# buffered_mult_rt1_postpwer.net
KiCad netlist of a schematic drawn in EAGLE
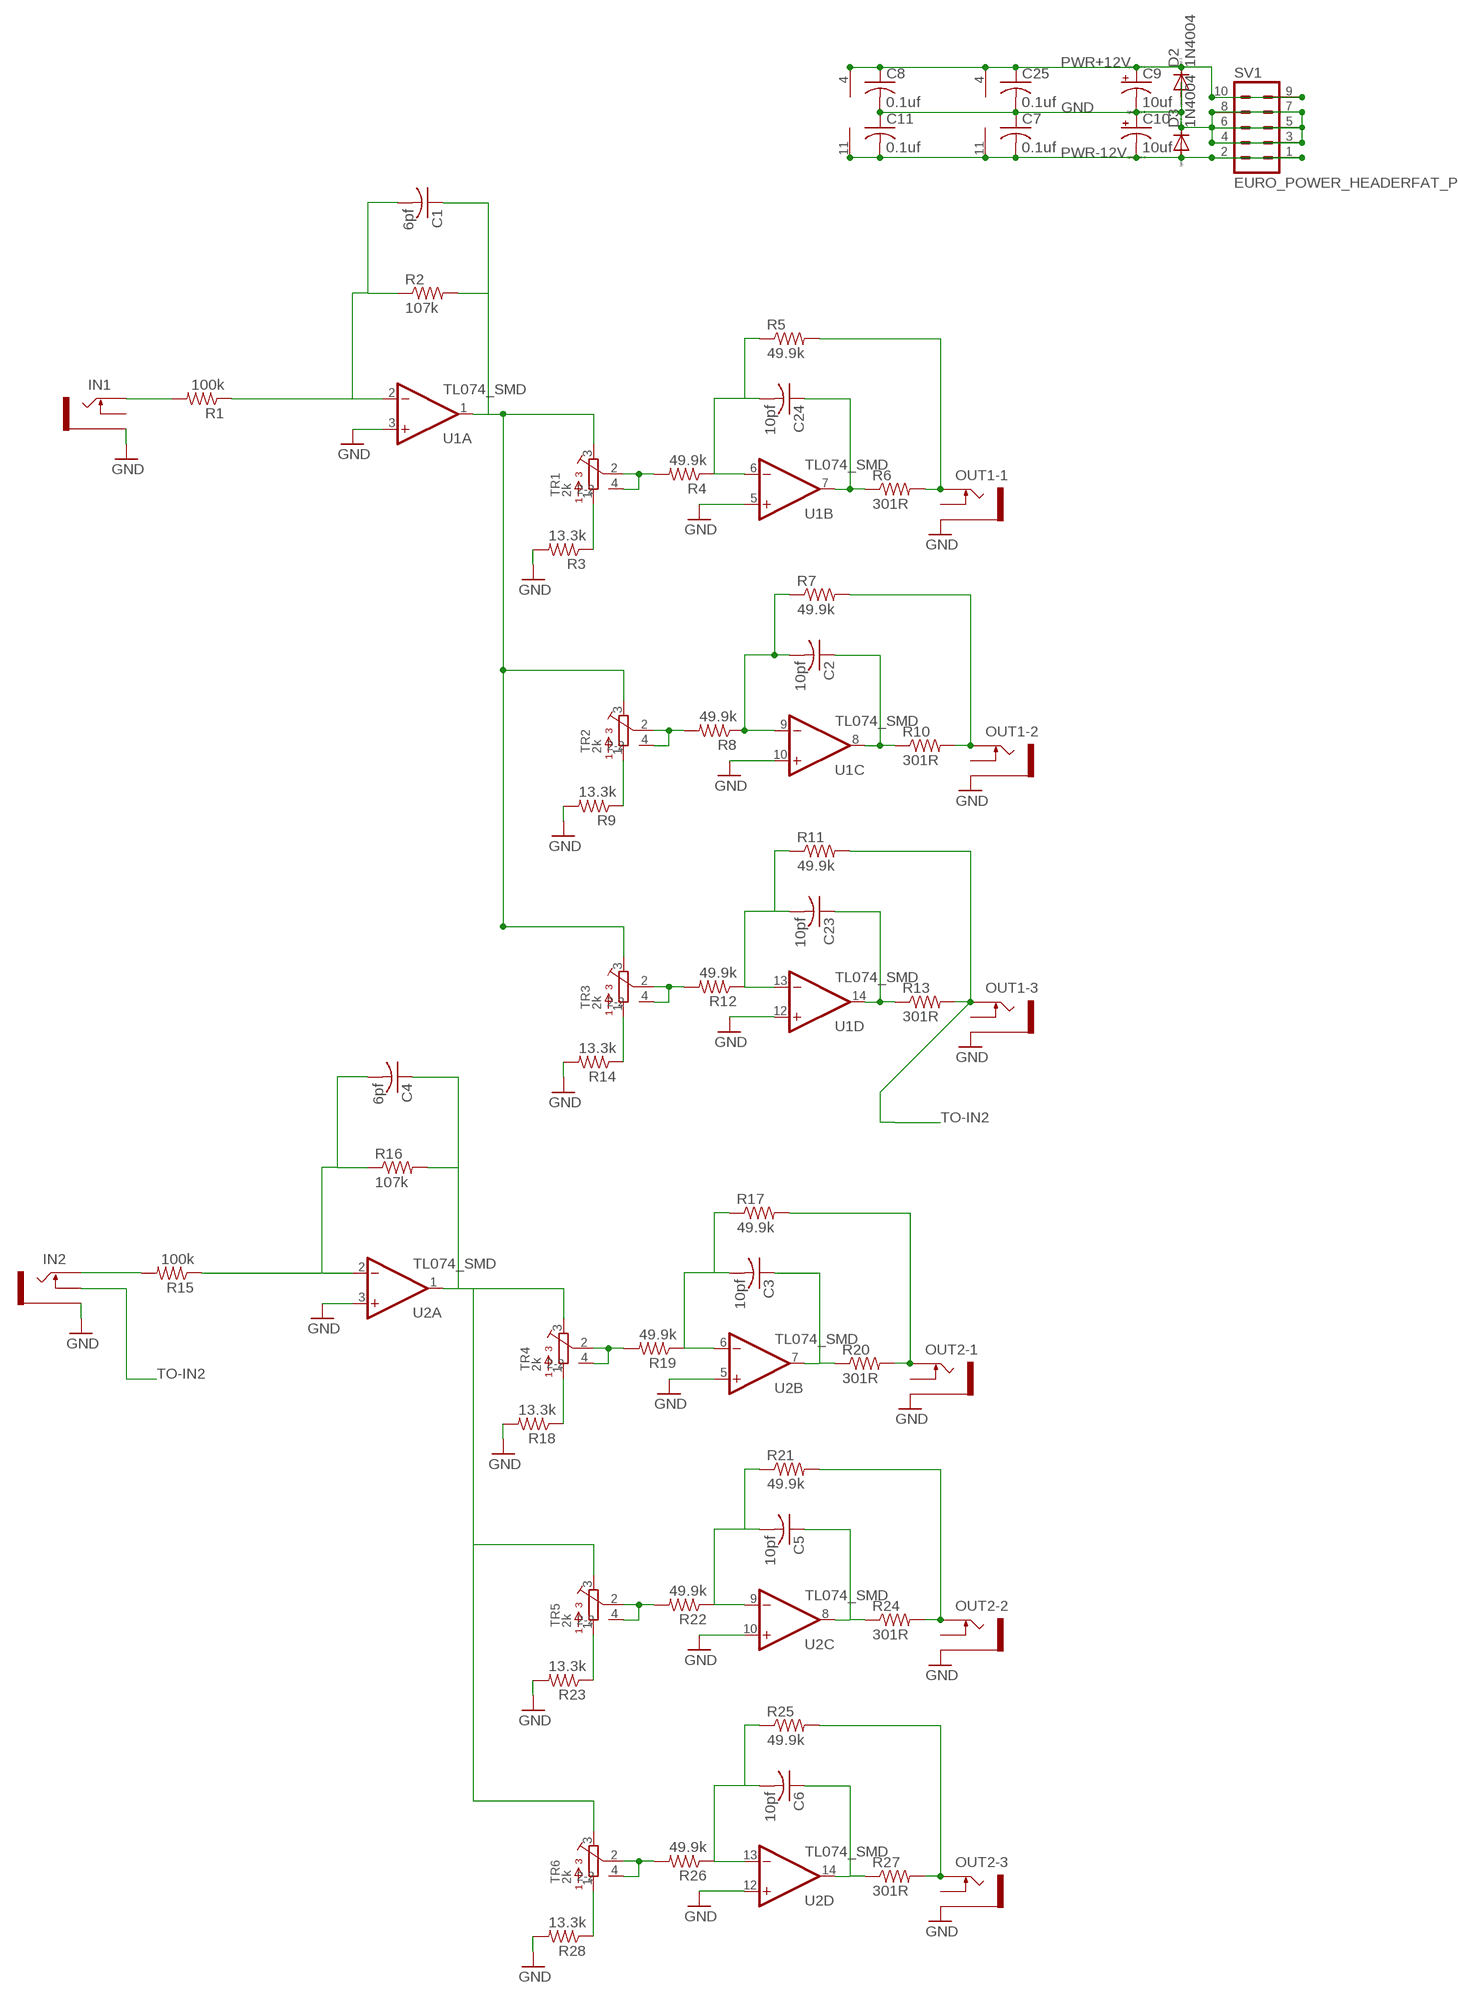
[diagram p0: schematic, sheet 1]

(export (version "E")
  (design (tool "Eeschema 10.0.6"))
  (components
    (comp (ref "C1")
      (value "6pf")
      (footprint "eagle-import:C0603")
      (libsource (lib "eagle-import") (part "C-USC0603"))
    )
    (comp (ref "C2")
      (value "10pf")
      (footprint "eagle-import:C0603")
      (libsource (lib "eagle-import") (part "C-USC0603"))
    )
    (comp (ref "C3")
      (value "10pf")
      (footprint "eagle-import:C0603")
      (libsource (lib "eagle-import") (part "C-USC0603"))
    )
    (comp (ref "C4")
      (value "6pf")
      (footprint "eagle-import:C0603")
      (libsource (lib "eagle-import") (part "C-USC0603"))
    )
    (comp (ref "C5")
      (value "10pf")
      (footprint "eagle-import:C0603")
      (libsource (lib "eagle-import") (part "C-USC0603"))
    )
    (comp (ref "C6")
      (value "10pf")
      (footprint "eagle-import:C0603")
      (libsource (lib "eagle-import") (part "C-USC0603"))
    )
    (comp (ref "C7")
      (value "0.1uf")
      (footprint "eagle-import:C0603")
      (libsource (lib "eagle-import") (part "C-USC0603"))
    )
    (comp (ref "C8")
      (value "0.1uf")
      (footprint "eagle-import:C0603")
      (libsource (lib "eagle-import") (part "C-USC0603"))
    )
    (comp (ref "C9")
      (value "10uf")
      (footprint "eagle-import:153CLV-0505")
      (libsource (lib "eagle-import") (part "CPOL-US153CLV-0505"))
    )
    (comp (ref "C10")
      (value "10uf")
      (footprint "eagle-import:153CLV-0505")
      (libsource (lib "eagle-import") (part "CPOL-US153CLV-0505"))
    )
    (comp (ref "C11")
      (value "0.1uf")
      (footprint "eagle-import:C0603")
      (libsource (lib "eagle-import") (part "C-USC0603"))
    )
    (comp (ref "C23")
      (value "10pf")
      (footprint "eagle-import:C0603")
      (libsource (lib "eagle-import") (part "C-USC0603"))
    )
    (comp (ref "C24")
      (value "10pf")
      (footprint "eagle-import:C0603")
      (libsource (lib "eagle-import") (part "C-USC0603"))
    )
    (comp (ref "C25")
      (value "0.1uf")
      (footprint "eagle-import:C0603")
      (libsource (lib "eagle-import") (part "C-USC0603"))
    )
    (comp (ref "D2")
      (value "1N4004")
      (footprint "eagle-import:DO41-10")
      (libsource (lib "eagle-import") (part "1N4004"))
    )
    (comp (ref "D3")
      (value "1N4004")
      (footprint "eagle-import:DO41-10")
      (libsource (lib "eagle-import") (part "1N4004"))
    )
    (comp (ref "IN1")
      (value "THONKICONNNEW")
      (footprint "eagle-import:WQP-PJ301M-12_JACK")
      (libsource (lib "eagle-import") (part "THONKICONNNEW"))
    )
    (comp (ref "IN2")
      (value "THONKICONNNEW")
      (footprint "eagle-import:WQP-PJ301M-12_JACK")
      (libsource (lib "eagle-import") (part "THONKICONNNEW"))
    )
    (comp (ref "OUT1-1")
      (value "THONKICONNNEW")
      (footprint "eagle-import:WQP-PJ301M-12_JACK")
      (libsource (lib "eagle-import") (part "THONKICONNNEW"))
    )
    (comp (ref "OUT1-2")
      (value "THONKICONNNEW")
      (footprint "eagle-import:WQP-PJ301M-12_JACK")
      (libsource (lib "eagle-import") (part "THONKICONNNEW"))
    )
    (comp (ref "OUT1-3")
      (value "THONKICONNNEW")
      (footprint "eagle-import:WQP-PJ301M-12_JACK")
      (libsource (lib "eagle-import") (part "THONKICONNNEW"))
    )
    (comp (ref "OUT2-1")
      (value "THONKICONNNEW")
      (footprint "eagle-import:WQP-PJ301M-12_JACK")
      (libsource (lib "eagle-import") (part "THONKICONNNEW"))
    )
    (comp (ref "OUT2-2")
      (value "THONKICONNNEW")
      (footprint "eagle-import:WQP-PJ301M-12_JACK")
      (libsource (lib "eagle-import") (part "THONKICONNNEW"))
    )
    (comp (ref "OUT2-3")
      (value "THONKICONNNEW")
      (footprint "eagle-import:WQP-PJ301M-12_JACK")
      (libsource (lib "eagle-import") (part "THONKICONNNEW"))
    )
    (comp (ref "R1")
      (value "100k")
      (footprint "eagle-import:R0603")
      (libsource (lib "eagle-import") (part "R-US_R0603"))
    )
    (comp (ref "R2")
      (value "107k")
      (footprint "eagle-import:R0603")
      (libsource (lib "eagle-import") (part "R-US_R0603"))
    )
    (comp (ref "R3")
      (value "13.3k")
      (footprint "eagle-import:R0603")
      (libsource (lib "eagle-import") (part "R-US_R0603"))
    )
    (comp (ref "R4")
      (value "49.9k")
      (footprint "eagle-import:R0603")
      (libsource (lib "eagle-import") (part "R-US_R0603"))
    )
    (comp (ref "R5")
      (value "49.9k")
      (footprint "eagle-import:R0603")
      (libsource (lib "eagle-import") (part "R-US_R0603"))
    )
    (comp (ref "R6")
      (value "301R")
      (footprint "eagle-import:R0603")
      (libsource (lib "eagle-import") (part "R-US_R0603"))
    )
    (comp (ref "R7")
      (value "49.9k")
      (footprint "eagle-import:R0603")
      (libsource (lib "eagle-import") (part "R-US_R0603"))
    )
    (comp (ref "R8")
      (value "49.9k")
      (footprint "eagle-import:R0603")
      (libsource (lib "eagle-import") (part "R-US_R0603"))
    )
    (comp (ref "R9")
      (value "13.3k")
      (footprint "eagle-import:R0603")
      (libsource (lib "eagle-import") (part "R-US_R0603"))
    )
    (comp (ref "R10")
      (value "301R")
      (footprint "eagle-import:R0603")
      (libsource (lib "eagle-import") (part "R-US_R0603"))
    )
    (comp (ref "R11")
      (value "49.9k")
      (footprint "eagle-import:R0603")
      (libsource (lib "eagle-import") (part "R-US_R0603"))
    )
    (comp (ref "R12")
      (value "49.9k")
      (footprint "eagle-import:R0603")
      (libsource (lib "eagle-import") (part "R-US_R0603"))
    )
    (comp (ref "R13")
      (value "301R")
      (footprint "eagle-import:R0603")
      (libsource (lib "eagle-import") (part "R-US_R0603"))
    )
    (comp (ref "R14")
      (value "13.3k")
      (footprint "eagle-import:R0603")
      (libsource (lib "eagle-import") (part "R-US_R0603"))
    )
    (comp (ref "R15")
      (value "100k")
      (footprint "eagle-import:R0603")
      (libsource (lib "eagle-import") (part "R-US_R0603"))
    )
    (comp (ref "R16")
      (value "107k")
      (footprint "eagle-import:R0603")
      (libsource (lib "eagle-import") (part "R-US_R0603"))
    )
    (comp (ref "R17")
      (value "49.9k")
      (footprint "eagle-import:R0603")
      (libsource (lib "eagle-import") (part "R-US_R0603"))
    )
    (comp (ref "R18")
      (value "13.3k")
      (footprint "eagle-import:R0603")
      (libsource (lib "eagle-import") (part "R-US_R0603"))
    )
    (comp (ref "R19")
      (value "49.9k")
      (footprint "eagle-import:R0603")
      (libsource (lib "eagle-import") (part "R-US_R0603"))
    )
    (comp (ref "R20")
      (value "301R")
      (footprint "eagle-import:R0603")
      (libsource (lib "eagle-import") (part "R-US_R0603"))
    )
    (comp (ref "R21")
      (value "49.9k")
      (footprint "eagle-import:R0603")
      (libsource (lib "eagle-import") (part "R-US_R0603"))
    )
    (comp (ref "R22")
      (value "49.9k")
      (footprint "eagle-import:R0603")
      (libsource (lib "eagle-import") (part "R-US_R0603"))
    )
    (comp (ref "R23")
      (value "13.3k")
      (footprint "eagle-import:R0603")
      (libsource (lib "eagle-import") (part "R-US_R0603"))
    )
    (comp (ref "R24")
      (value "301R")
      (footprint "eagle-import:R0603")
      (libsource (lib "eagle-import") (part "R-US_R0603"))
    )
    (comp (ref "R25")
      (value "49.9k")
      (footprint "eagle-import:R0603")
      (libsource (lib "eagle-import") (part "R-US_R0603"))
    )
    (comp (ref "R26")
      (value "49.9k")
      (footprint "eagle-import:R0603")
      (libsource (lib "eagle-import") (part "R-US_R0603"))
    )
    (comp (ref "R27")
      (value "301R")
      (footprint "eagle-import:R0603")
      (libsource (lib "eagle-import") (part "R-US_R0603"))
    )
    (comp (ref "R28")
      (value "13.3k")
      (footprint "eagle-import:R0603")
      (libsource (lib "eagle-import") (part "R-US_R0603"))
    )
    (comp (ref "SV1")
      (value "EURO_POWER_HEADERFAT_PADS")
      (footprint "eagle-import:EURO_PWR_HEADER_FAT")
      (libsource (lib "eagle-import") (part "EURO_POWER_HEADERFAT_PADS"))
    )
    (comp (ref "TR1")
      (value "2k")
      (footprint "eagle-import:BOURNS_3362P_TRIMMER")
      (libsource (lib "eagle-import") (part "BOURNS_3362P_TRIMMERP"))
    )
    (comp (ref "TR2")
      (value "2k")
      (footprint "eagle-import:BOURNS_3362P_TRIMMER")
      (libsource (lib "eagle-import") (part "BOURNS_3362P_TRIMMERP"))
    )
    (comp (ref "TR3")
      (value "2k")
      (footprint "eagle-import:BOURNS_3362P_TRIMMER")
      (libsource (lib "eagle-import") (part "BOURNS_3362P_TRIMMERP"))
    )
    (comp (ref "TR4")
      (value "2k")
      (footprint "eagle-import:BOURNS_3362P_TRIMMER")
      (libsource (lib "eagle-import") (part "BOURNS_3362P_TRIMMERP"))
    )
    (comp (ref "TR5")
      (value "2k")
      (footprint "eagle-import:BOURNS_3362P_TRIMMER")
      (libsource (lib "eagle-import") (part "BOURNS_3362P_TRIMMERP"))
    )
    (comp (ref "TR6")
      (value "2k")
      (footprint "eagle-import:BOURNS_3362P_TRIMMER")
      (libsource (lib "eagle-import") (part "BOURNS_3362P_TRIMMERP"))
    )
    (comp (ref "U1")
      (value "TL074_SMD")
      (footprint "eagle-import:SO14")
      (libsource (lib "eagle-import") (part "TL074_SMD"))
    )
    (comp (ref "U2")
      (value "TL074_SMD")
      (footprint "eagle-import:SO14")
      (libsource (lib "eagle-import") (part "TL074_SMD"))
    )
  )
  (nets
    (net (code "1") (name "GND") (class "Default")
      (node (ref "C10") (pin "+") (pinfunction "+_+") (pintype "passive"))
      (node (ref "C11") (pin "1") (pinfunction "1_1") (pintype "passive"))
      (node (ref "C25") (pin "2") (pinfunction "2_2") (pintype "passive"))
      (node (ref "C7") (pin "1") (pinfunction "1_1") (pintype "passive"))
      (node (ref "C8") (pin "2") (pinfunction "2_2") (pintype "passive"))
      (node (ref "C9") (pin "-") (pinfunction "-_-") (pintype "passive"))
      (node (ref "D2") (pin "A") (pinfunction "A_A") (pintype "passive"))
      (node (ref "D3") (pin "C") (pinfunction "C_C") (pintype "passive"))
      (node (ref "IN1") (pin "P$3_SLEEVE") (pinfunction "SLEEVE_P$3_SLEEVE") (pintype "passive"))
      (node (ref "IN2") (pin "P$3_SLEEVE") (pinfunction "SLEEVE_P$3_SLEEVE") (pintype "passive"))
      (node (ref "OUT1-1") (pin "P$3_SLEEVE") (pinfunction "SLEEVE_P$3_SLEEVE") (pintype "passive"))
      (node (ref "OUT1-2") (pin "P$3_SLEEVE") (pinfunction "SLEEVE_P$3_SLEEVE") (pintype "passive"))
      (node (ref "OUT1-3") (pin "P$3_SLEEVE") (pinfunction "SLEEVE_P$3_SLEEVE") (pintype "passive"))
      (node (ref "OUT2-1") (pin "P$3_SLEEVE") (pinfunction "SLEEVE_P$3_SLEEVE") (pintype "passive"))
      (node (ref "OUT2-2") (pin "P$3_SLEEVE") (pinfunction "SLEEVE_P$3_SLEEVE") (pintype "passive"))
      (node (ref "OUT2-3") (pin "P$3_SLEEVE") (pinfunction "SLEEVE_P$3_SLEEVE") (pintype "passive"))
      (node (ref "R14") (pin "2") (pinfunction "2_2") (pintype "passive"))
      (node (ref "R18") (pin "2") (pinfunction "2_2") (pintype "passive"))
      (node (ref "R23") (pin "2") (pinfunction "2_2") (pintype "passive"))
      (node (ref "R28") (pin "2") (pinfunction "2_2") (pintype "passive"))
      (node (ref "R3") (pin "2") (pinfunction "2_2") (pintype "passive"))
      (node (ref "R9") (pin "2") (pinfunction "2_2") (pintype "passive"))
      (node (ref "SV1") (pin "3") (pinfunction "3_3") (pintype "passive"))
      (node (ref "SV1") (pin "4") (pinfunction "4_4") (pintype "passive"))
      (node (ref "SV1") (pin "5") (pinfunction "5_5") (pintype "passive"))
      (node (ref "SV1") (pin "6") (pinfunction "6_6") (pintype "passive"))
      (node (ref "SV1") (pin "7") (pinfunction "7_7") (pintype "passive"))
      (node (ref "SV1") (pin "8") (pinfunction "8_8") (pintype "passive"))
      (node (ref "U1") (pin "10") (pinfunction "+IN_10") (pintype "input"))
      (node (ref "U1") (pin "12") (pinfunction "+IN_12") (pintype "input"))
      (node (ref "U1") (pin "3") (pinfunction "+IN_3") (pintype "input"))
      (node (ref "U1") (pin "5") (pinfunction "+IN_5") (pintype "input"))
      (node (ref "U2") (pin "10") (pinfunction "+IN_10") (pintype "input"))
      (node (ref "U2") (pin "12") (pinfunction "+IN_12") (pintype "input"))
      (node (ref "U2") (pin "3") (pinfunction "+IN_3") (pintype "input"))
      (node (ref "U2") (pin "5") (pinfunction "+IN_5") (pintype "input"))
    )
    (net (code "2") (name "Net-(IN1-TIP)") (class "Default")
      (node (ref "IN1") (pin "P$1_TIP") (pinfunction "TIP_P$1_TIP") (pintype "passive"))
      (node (ref "R1") (pin "2") (pinfunction "2_2") (pintype "passive"))
    )
    (net (code "3") (name "Net-(IN2-TIP)") (class "Default")
      (node (ref "IN2") (pin "P$1_TIP") (pinfunction "TIP_P$1_TIP") (pintype "passive"))
      (node (ref "R15") (pin "2") (pinfunction "2_2") (pintype "passive"))
    )
    (net (code "4") (name "Net-(OUT1-1-TIP)") (class "Default")
      (node (ref "OUT1-1") (pin "P$1_TIP") (pinfunction "TIP_P$1_TIP") (pintype "passive"))
      (node (ref "R5") (pin "2") (pinfunction "2_2") (pintype "passive"))
      (node (ref "R6") (pin "2") (pinfunction "2_2") (pintype "passive"))
    )
    (net (code "5") (name "Net-(OUT1-2-TIP)") (class "Default")
      (node (ref "OUT1-2") (pin "P$1_TIP") (pinfunction "TIP_P$1_TIP") (pintype "passive"))
      (node (ref "R10") (pin "2") (pinfunction "2_2") (pintype "passive"))
      (node (ref "R7") (pin "2") (pinfunction "2_2") (pintype "passive"))
    )
    (net (code "6") (name "Net-(OUT2-1-TIP)") (class "Default")
      (node (ref "OUT2-1") (pin "P$1_TIP") (pinfunction "TIP_P$1_TIP") (pintype "passive"))
      (node (ref "R17") (pin "2") (pinfunction "2_2") (pintype "passive"))
      (node (ref "R20") (pin "2") (pinfunction "2_2") (pintype "passive"))
    )
    (net (code "7") (name "Net-(OUT2-2-TIP)") (class "Default")
      (node (ref "OUT2-2") (pin "P$1_TIP") (pinfunction "TIP_P$1_TIP") (pintype "passive"))
      (node (ref "R21") (pin "2") (pinfunction "2_2") (pintype "passive"))
      (node (ref "R24") (pin "2") (pinfunction "2_2") (pintype "passive"))
    )
    (net (code "8") (name "Net-(OUT2-3-TIP)") (class "Default")
      (node (ref "OUT2-3") (pin "P$1_TIP") (pinfunction "TIP_P$1_TIP") (pintype "passive"))
      (node (ref "R25") (pin "2") (pinfunction "2_2") (pintype "passive"))
      (node (ref "R27") (pin "2") (pinfunction "2_2") (pintype "passive"))
    )
    (net (code "9") (name "Net-(R3-Pad1)") (class "Default")
      (node (ref "R3") (pin "1") (pinfunction "1_1") (pintype "passive"))
      (node (ref "TR1") (pin "1") (pinfunction "1_1") (pintype "passive"))
    )
    (net (code "10") (name "Net-(R9-Pad1)") (class "Default")
      (node (ref "R9") (pin "1") (pinfunction "1_1") (pintype "passive"))
      (node (ref "TR2") (pin "1") (pinfunction "1_1") (pintype "passive"))
    )
    (net (code "11") (name "Net-(R14-Pad1)") (class "Default")
      (node (ref "R14") (pin "1") (pinfunction "1_1") (pintype "passive"))
      (node (ref "TR3") (pin "1") (pinfunction "1_1") (pintype "passive"))
    )
    (net (code "12") (name "Net-(R18-Pad1)") (class "Default")
      (node (ref "R18") (pin "1") (pinfunction "1_1") (pintype "passive"))
      (node (ref "TR4") (pin "1") (pinfunction "1_1") (pintype "passive"))
    )
    (net (code "13") (name "Net-(R23-Pad1)") (class "Default")
      (node (ref "R23") (pin "1") (pinfunction "1_1") (pintype "passive"))
      (node (ref "TR5") (pin "1") (pinfunction "1_1") (pintype "passive"))
    )
    (net (code "14") (name "Net-(R28-Pad1)") (class "Default")
      (node (ref "R28") (pin "1") (pinfunction "1_1") (pintype "passive"))
      (node (ref "TR6") (pin "1") (pinfunction "1_1") (pintype "passive"))
    )
    (net (code "15") (name "Net-(TR1-2-2)") (class "Default")
      (node (ref "R4") (pin "2") (pinfunction "2_2") (pintype "passive"))
      (node (ref "TR1") (pin "2") (pinfunction "2_2") (pintype "passive"))
      (node (ref "TR1") (pin "4") (pinfunction "2-2_4") (pintype "bidirectional"))
    )
    (net (code "16") (name "Net-(TR2-2-2)") (class "Default")
      (node (ref "R8") (pin "2") (pinfunction "2_2") (pintype "passive"))
      (node (ref "TR2") (pin "2") (pinfunction "2_2") (pintype "passive"))
      (node (ref "TR2") (pin "4") (pinfunction "2-2_4") (pintype "bidirectional"))
    )
    (net (code "17") (name "Net-(TR3-2-2)") (class "Default")
      (node (ref "R12") (pin "2") (pinfunction "2_2") (pintype "passive"))
      (node (ref "TR3") (pin "2") (pinfunction "2_2") (pintype "passive"))
      (node (ref "TR3") (pin "4") (pinfunction "2-2_4") (pintype "bidirectional"))
    )
    (net (code "18") (name "Net-(TR4-2-2)") (class "Default")
      (node (ref "R19") (pin "2") (pinfunction "2_2") (pintype "passive"))
      (node (ref "TR4") (pin "2") (pinfunction "2_2") (pintype "passive"))
      (node (ref "TR4") (pin "4") (pinfunction "2-2_4") (pintype "bidirectional"))
    )
    (net (code "19") (name "Net-(TR5-2-2)") (class "Default")
      (node (ref "R22") (pin "2") (pinfunction "2_2") (pintype "passive"))
      (node (ref "TR5") (pin "2") (pinfunction "2_2") (pintype "passive"))
      (node (ref "TR5") (pin "4") (pinfunction "2-2_4") (pintype "bidirectional"))
    )
    (net (code "20") (name "Net-(TR6-2-2)") (class "Default")
      (node (ref "R26") (pin "2") (pinfunction "2_2") (pintype "passive"))
      (node (ref "TR6") (pin "2") (pinfunction "2_2") (pintype "passive"))
      (node (ref "TR6") (pin "4") (pinfunction "2-2_4") (pintype "bidirectional"))
    )
    (net (code "21") (name "Net-(U1A--IN)") (class "Default")
      (node (ref "C1") (pin "2") (pinfunction "2_2") (pintype "passive"))
      (node (ref "R1") (pin "1") (pinfunction "1_1") (pintype "passive"))
      (node (ref "R2") (pin "1") (pinfunction "1_1") (pintype "passive"))
      (node (ref "U1") (pin "2") (pinfunction "-IN_2") (pintype "input"))
    )
    (net (code "22") (name "Net-(U1A-OUT)") (class "Default")
      (node (ref "C1") (pin "1") (pinfunction "1_1") (pintype "passive"))
      (node (ref "R2") (pin "2") (pinfunction "2_2") (pintype "passive"))
      (node (ref "TR1") (pin "3") (pinfunction "3_3") (pintype "passive"))
      (node (ref "TR2") (pin "3") (pinfunction "3_3") (pintype "passive"))
      (node (ref "TR3") (pin "3") (pinfunction "3_3") (pintype "passive"))
      (node (ref "U1") (pin "1") (pinfunction "OUT_1") (pintype "output"))
    )
    (net (code "23") (name "Net-(U1B--IN)") (class "Default")
      (node (ref "C24") (pin "2") (pinfunction "2_2") (pintype "passive"))
      (node (ref "R4") (pin "1") (pinfunction "1_1") (pintype "passive"))
      (node (ref "R5") (pin "1") (pinfunction "1_1") (pintype "passive"))
      (node (ref "U1") (pin "6") (pinfunction "-IN_6") (pintype "input"))
    )
    (net (code "24") (name "Net-(U1B-OUT)") (class "Default")
      (node (ref "C24") (pin "1") (pinfunction "1_1") (pintype "passive"))
      (node (ref "R6") (pin "1") (pinfunction "1_1") (pintype "passive"))
      (node (ref "U1") (pin "7") (pinfunction "OUT_7") (pintype "output"))
    )
    (net (code "25") (name "Net-(U1C--IN)") (class "Default")
      (node (ref "C2") (pin "2") (pinfunction "2_2") (pintype "passive"))
      (node (ref "R7") (pin "1") (pinfunction "1_1") (pintype "passive"))
      (node (ref "R8") (pin "1") (pinfunction "1_1") (pintype "passive"))
      (node (ref "U1") (pin "9") (pinfunction "-IN_9") (pintype "input"))
    )
    (net (code "26") (name "Net-(U1C-OUT)") (class "Default")
      (node (ref "C2") (pin "1") (pinfunction "1_1") (pintype "passive"))
      (node (ref "R10") (pin "1") (pinfunction "1_1") (pintype "passive"))
      (node (ref "U1") (pin "8") (pinfunction "OUT_8") (pintype "output"))
    )
    (net (code "27") (name "Net-(U1D--IN)") (class "Default")
      (node (ref "C23") (pin "2") (pinfunction "2_2") (pintype "passive"))
      (node (ref "R11") (pin "1") (pinfunction "1_1") (pintype "passive"))
      (node (ref "R12") (pin "1") (pinfunction "1_1") (pintype "passive"))
      (node (ref "U1") (pin "13") (pinfunction "-IN_13") (pintype "input"))
    )
    (net (code "28") (name "Net-(U2A--IN)") (class "Default")
      (node (ref "C4") (pin "2") (pinfunction "2_2") (pintype "passive"))
      (node (ref "R15") (pin "1") (pinfunction "1_1") (pintype "passive"))
      (node (ref "R16") (pin "1") (pinfunction "1_1") (pintype "passive"))
      (node (ref "U2") (pin "2") (pinfunction "-IN_2") (pintype "input"))
    )
    (net (code "29") (name "Net-(U2A-OUT)") (class "Default")
      (node (ref "C4") (pin "1") (pinfunction "1_1") (pintype "passive"))
      (node (ref "R16") (pin "2") (pinfunction "2_2") (pintype "passive"))
      (node (ref "TR4") (pin "3") (pinfunction "3_3") (pintype "passive"))
      (node (ref "TR5") (pin "3") (pinfunction "3_3") (pintype "passive"))
      (node (ref "TR6") (pin "3") (pinfunction "3_3") (pintype "passive"))
      (node (ref "U2") (pin "1") (pinfunction "OUT_1") (pintype "output"))
    )
    (net (code "30") (name "Net-(U2B--IN)") (class "Default")
      (node (ref "C3") (pin "2") (pinfunction "2_2") (pintype "passive"))
      (node (ref "R17") (pin "1") (pinfunction "1_1") (pintype "passive"))
      (node (ref "R19") (pin "1") (pinfunction "1_1") (pintype "passive"))
      (node (ref "U2") (pin "6") (pinfunction "-IN_6") (pintype "input"))
    )
    (net (code "31") (name "Net-(U2B-OUT)") (class "Default")
      (node (ref "C3") (pin "1") (pinfunction "1_1") (pintype "passive"))
      (node (ref "R20") (pin "1") (pinfunction "1_1") (pintype "passive"))
      (node (ref "U2") (pin "7") (pinfunction "OUT_7") (pintype "output"))
    )
    (net (code "32") (name "Net-(U2C--IN)") (class "Default")
      (node (ref "C5") (pin "2") (pinfunction "2_2") (pintype "passive"))
      (node (ref "R21") (pin "1") (pinfunction "1_1") (pintype "passive"))
      (node (ref "R22") (pin "1") (pinfunction "1_1") (pintype "passive"))
      (node (ref "U2") (pin "9") (pinfunction "-IN_9") (pintype "input"))
    )
    (net (code "33") (name "Net-(U2C-OUT)") (class "Default")
      (node (ref "C5") (pin "1") (pinfunction "1_1") (pintype "passive"))
      (node (ref "R24") (pin "1") (pinfunction "1_1") (pintype "passive"))
      (node (ref "U2") (pin "8") (pinfunction "OUT_8") (pintype "output"))
    )
    (net (code "34") (name "Net-(U2D--IN)") (class "Default")
      (node (ref "C6") (pin "2") (pinfunction "2_2") (pintype "passive"))
      (node (ref "R25") (pin "1") (pinfunction "1_1") (pintype "passive"))
      (node (ref "R26") (pin "1") (pinfunction "1_1") (pintype "passive"))
      (node (ref "U2") (pin "13") (pinfunction "-IN_13") (pintype "input"))
    )
    (net (code "35") (name "Net-(U2D-OUT)") (class "Default")
      (node (ref "C6") (pin "1") (pinfunction "1_1") (pintype "passive"))
      (node (ref "R27") (pin "1") (pinfunction "1_1") (pintype "passive"))
      (node (ref "U2") (pin "14") (pinfunction "OUT_14") (pintype "output"))
    )
    (net (code "36") (name "PWR+12V") (class "Default")
      (node (ref "C25") (pin "1") (pinfunction "1_1") (pintype "passive"))
      (node (ref "C8") (pin "1") (pinfunction "1_1") (pintype "passive"))
      (node (ref "C9") (pin "+") (pinfunction "+_+") (pintype "passive"))
      (node (ref "D2") (pin "C") (pinfunction "C_C") (pintype "passive"))
      (node (ref "SV1") (pin "10") (pinfunction "10_10") (pintype "passive"))
      (node (ref "SV1") (pin "9") (pinfunction "9_9") (pintype "passive"))
      (node (ref "U1") (pin "4") (pinfunction "V+_4") (pintype "power_in"))
      (node (ref "U2") (pin "4") (pinfunction "V+_4") (pintype "power_in"))
    )
    (net (code "37") (name "PWR-12V") (class "Default")
      (node (ref "C10") (pin "-") (pinfunction "-_-") (pintype "passive"))
      (node (ref "C11") (pin "2") (pinfunction "2_2") (pintype "passive"))
      (node (ref "C7") (pin "2") (pinfunction "2_2") (pintype "passive"))
      (node (ref "D3") (pin "A") (pinfunction "A_A") (pintype "passive"))
      (node (ref "SV1") (pin "1") (pinfunction "1_1") (pintype "passive"))
      (node (ref "SV1") (pin "2") (pinfunction "2_2") (pintype "passive"))
      (node (ref "U1") (pin "11") (pinfunction "V-_11") (pintype "power_in"))
      (node (ref "U2") (pin "11") (pinfunction "V-_11") (pintype "power_in"))
    )
    (net (code "38") (name "TO-IN2") (class "Default")
      (node (ref "C23") (pin "1") (pinfunction "1_1") (pintype "passive"))
      (node (ref "IN2") (pin "P$2_SWITCH") (pinfunction "SWITCH_P$2_SWITCH") (pintype "passive"))
      (node (ref "OUT1-3") (pin "P$1_TIP") (pinfunction "TIP_P$1_TIP") (pintype "passive"))
      (node (ref "R11") (pin "2") (pinfunction "2_2") (pintype "passive"))
      (node (ref "R13") (pin "1") (pinfunction "1_1") (pintype "passive"))
      (node (ref "R13") (pin "2") (pinfunction "2_2") (pintype "passive"))
      (node (ref "U1") (pin "14") (pinfunction "OUT_14") (pintype "output"))
    )
    (net (code "39") (name "unconnected-(IN1-SWITCH-PadP$2_SWITCH)") (class "Default")
      (node (ref "IN1") (pin "P$2_SWITCH") (pinfunction "SWITCH_P$2_SWITCH") (pintype "passive"))
    )
    (net (code "40") (name "unconnected-(OUT1-1-SWITCH-PadP$2_SWITCH)") (class "Default")
      (node (ref "OUT1-1") (pin "P$2_SWITCH") (pinfunction "SWITCH_P$2_SWITCH") (pintype "passive"))
    )
    (net (code "41") (name "unconnected-(OUT1-2-SWITCH-PadP$2_SWITCH)") (class "Default")
      (node (ref "OUT1-2") (pin "P$2_SWITCH") (pinfunction "SWITCH_P$2_SWITCH") (pintype "passive"))
    )
    (net (code "42") (name "unconnected-(OUT1-3-SWITCH-PadP$2_SWITCH)") (class "Default")
      (node (ref "OUT1-3") (pin "P$2_SWITCH") (pinfunction "SWITCH_P$2_SWITCH") (pintype "passive"))
    )
    (net (code "43") (name "unconnected-(OUT2-1-SWITCH-PadP$2_SWITCH)") (class "Default")
      (node (ref "OUT2-1") (pin "P$2_SWITCH") (pinfunction "SWITCH_P$2_SWITCH") (pintype "passive"))
    )
    (net (code "44") (name "unconnected-(OUT2-2-SWITCH-PadP$2_SWITCH)") (class "Default")
      (node (ref "OUT2-2") (pin "P$2_SWITCH") (pinfunction "SWITCH_P$2_SWITCH") (pintype "passive"))
    )
    (net (code "45") (name "unconnected-(OUT2-3-SWITCH-PadP$2_SWITCH)") (class "Default")
      (node (ref "OUT2-3") (pin "P$2_SWITCH") (pinfunction "SWITCH_P$2_SWITCH") (pintype "passive"))
    )
  )
)
